# Display_Board_v2.net
KiCad netlist of a schematic drawn in EAGLE
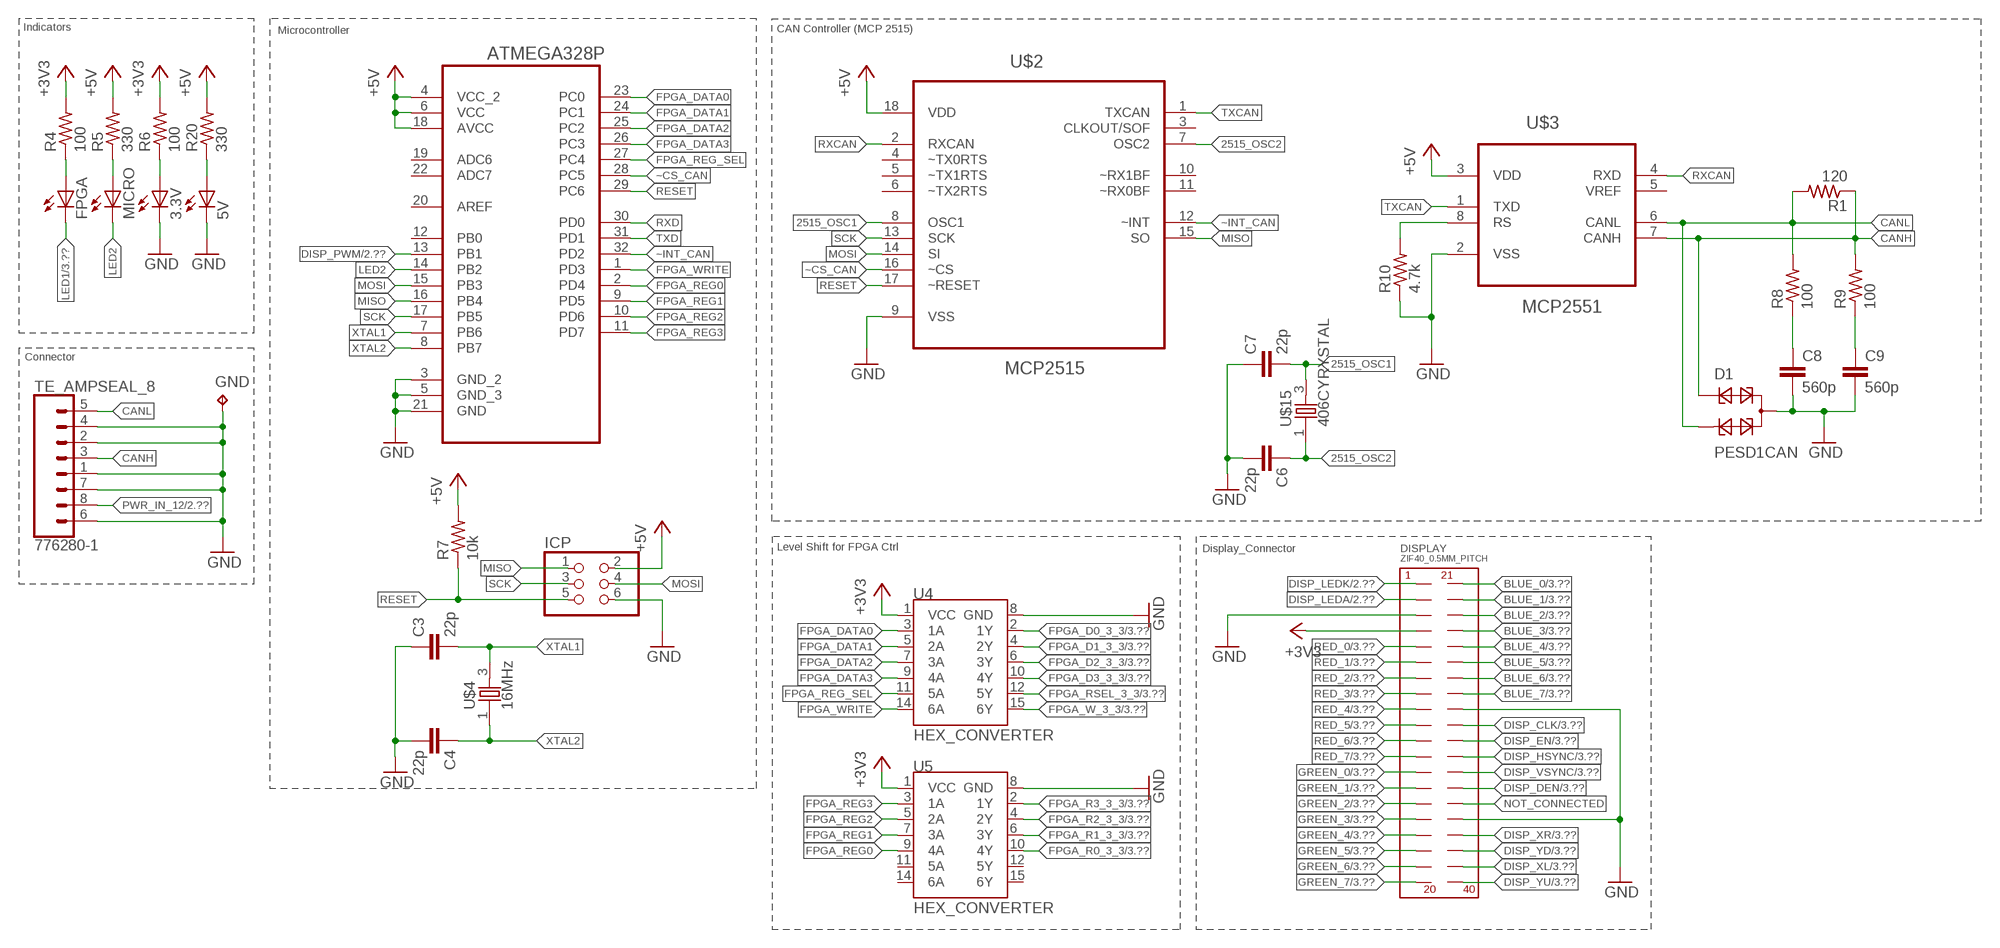
[diagram p0: schematic, sheet 1]
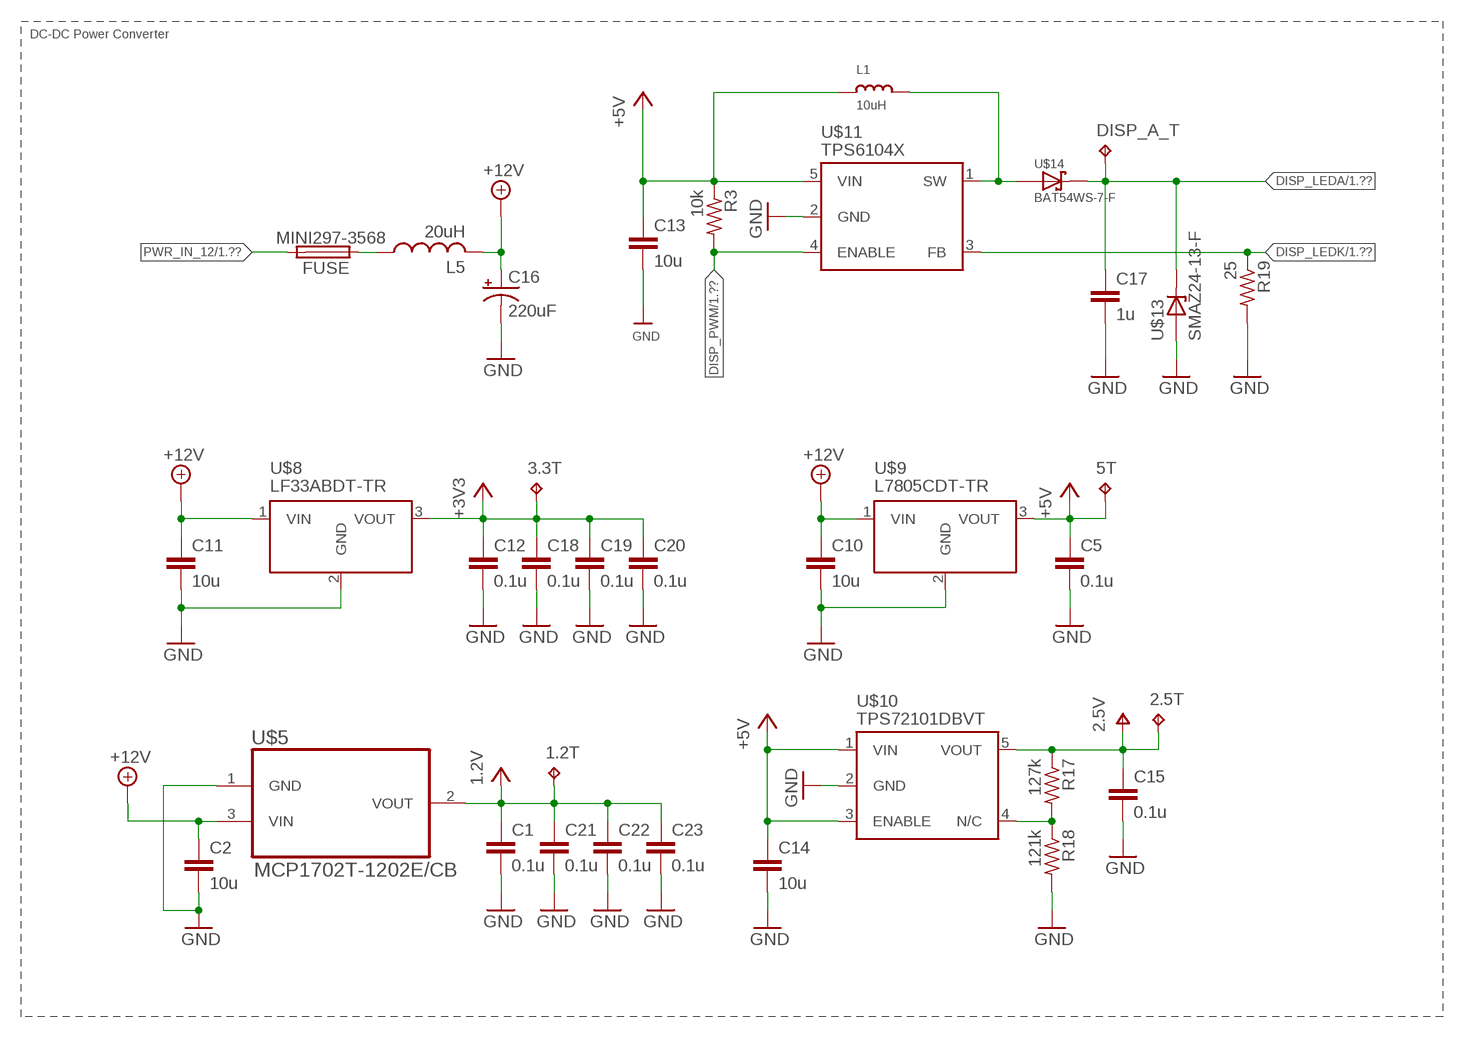
[diagram p1: schematic, sheet 2]
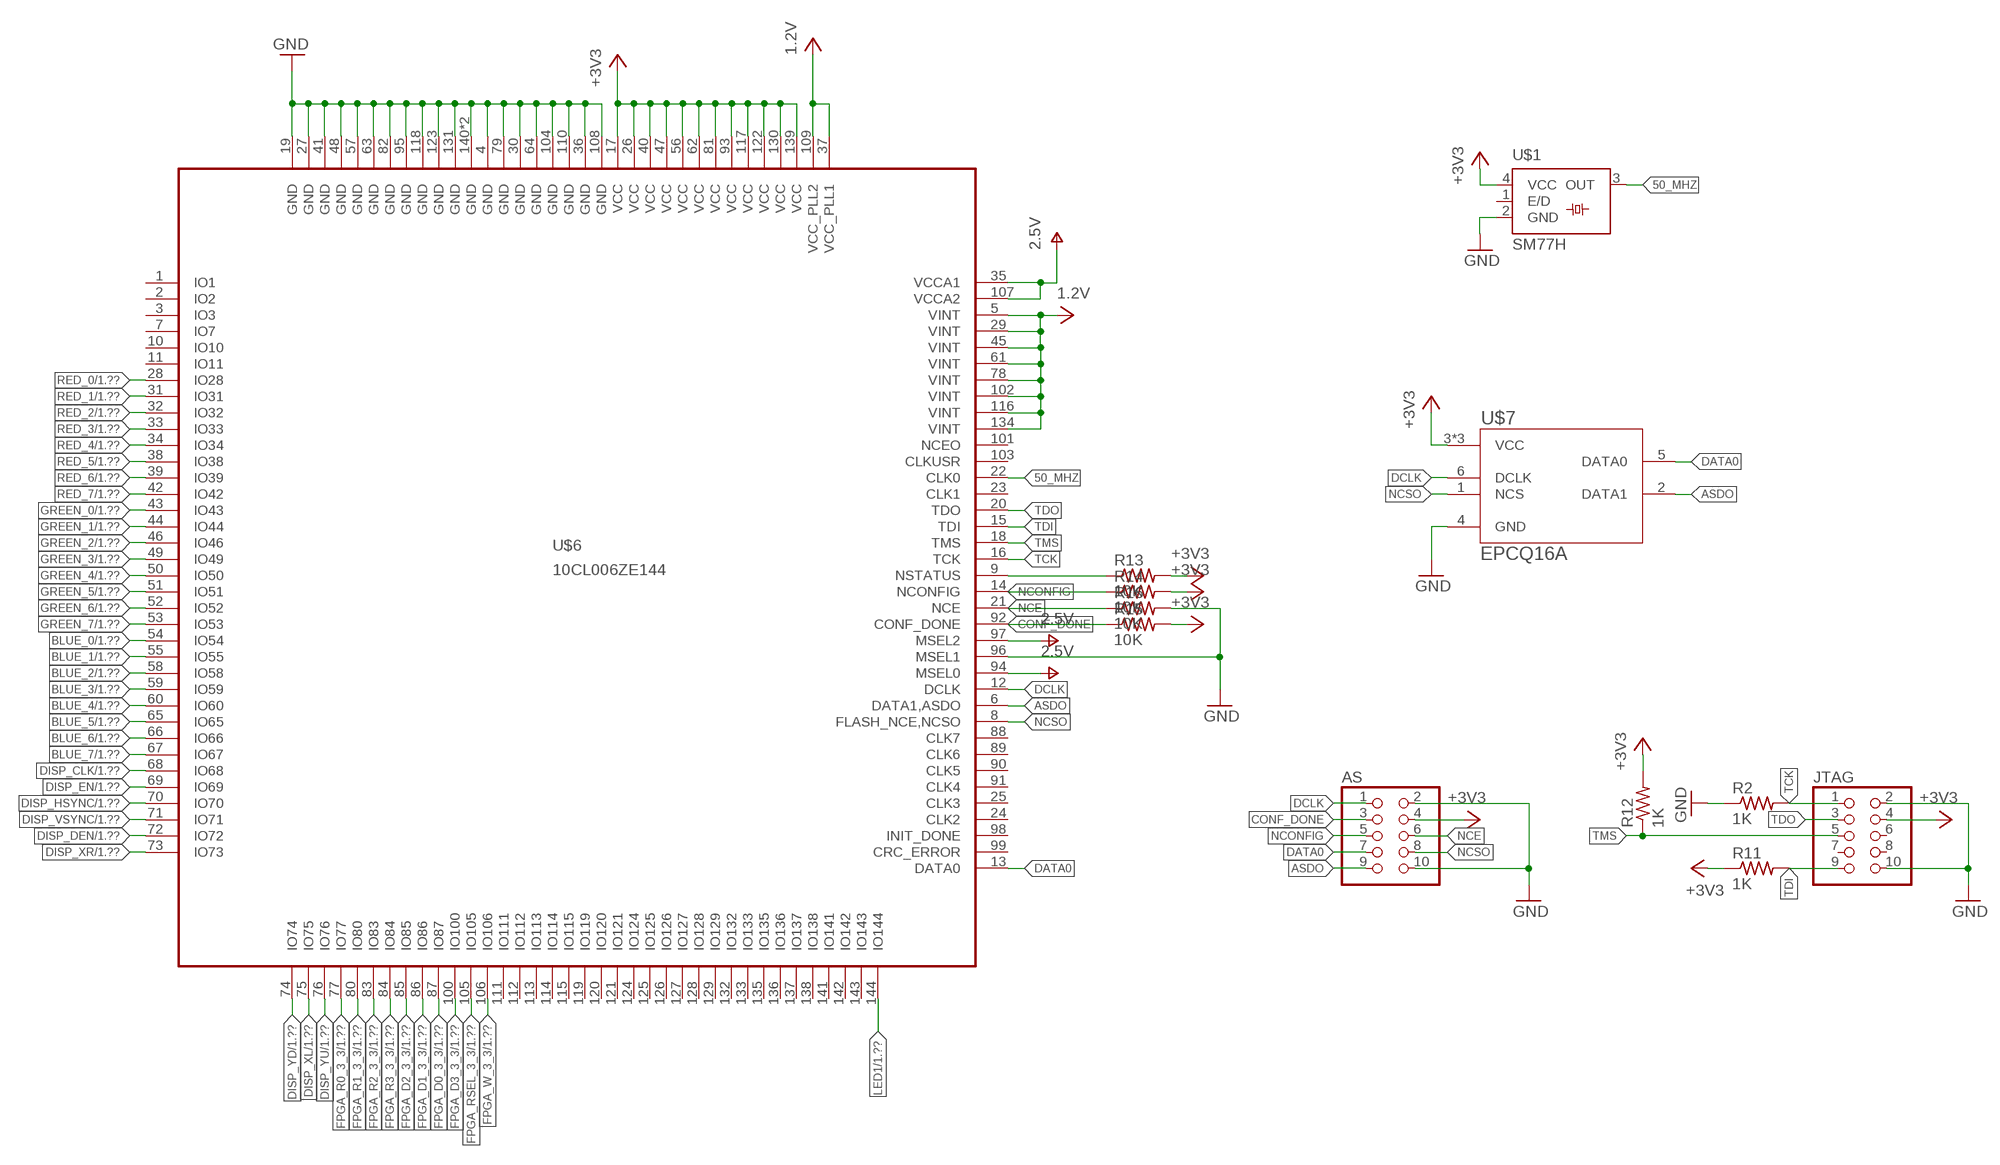
[diagram p2: schematic, sheet 3]

(export (version "E")
  (design (tool "Eeschema 10.0.6"))
  (components
    (comp (ref "AS")
      (value "PINHD-2X5")
      (footprint "eagle-import:2X05")
      (libsource (lib "eagle-import") (part "PINHD-2X5"))
    )
    (comp (ref "JTAG")
      (value "PINHD-2X5")
      (footprint "eagle-import:2X05")
      (libsource (lib "eagle-import") (part "PINHD-2X5"))
    )
    (comp (ref "R2")
      (value "1K")
      (footprint "eagle-import:R0805")
      (libsource (lib "eagle-import") (part "resistor_R-US_R0805"))
    )
    (comp (ref "R11")
      (value "1K")
      (footprint "eagle-import:R0805")
      (libsource (lib "eagle-import") (part "resistor_R-US_R0805"))
    )
    (comp (ref "R12")
      (value "1K")
      (footprint "eagle-import:R0805")
      (libsource (lib "eagle-import") (part "resistor_R-US_R0805"))
    )
    (comp (ref "R13")
      (value "10K")
      (footprint "eagle-import:R0805")
      (libsource (lib "eagle-import") (part "resistor_R-US_R0805"))
    )
    (comp (ref "R14")
      (value "10K")
      (footprint "eagle-import:R0805")
      (libsource (lib "eagle-import") (part "resistor_R-US_R0805"))
    )
    (comp (ref "R15")
      (value "10K")
      (footprint "eagle-import:R0805")
      (libsource (lib "eagle-import") (part "resistor_R-US_R0805"))
    )
    (comp (ref "R16")
      (value "10K")
      (footprint "eagle-import:R0805")
      (libsource (lib "eagle-import") (part "resistor_R-US_R0805"))
    )
    (comp (ref "U$1")
      (value "SM77H")
      (footprint "eagle-import:SM77H")
      (libsource (lib "eagle-import") (part "SM77H"))
    )
    (comp (ref "U$6")
      (value "10CL006ZE144")
      (footprint "eagle-import:EQFP144")
      (libsource (lib "eagle-import") (part "10CL006ZE144"))
    )
    (comp (ref "U$7")
      (value "EPCQ16A")
      (footprint "eagle-import:SOIC127P600X175-8N")
      (libsource (lib "eagle-import") (part "EPCQ16A"))
    )
    (comp (ref "1.2T")
      (value "TPTP12SQ")
      (footprint "eagle-import:TP12SQ")
      (libsource (lib "eagle-import") (part "TPTP12SQ"))
    )
    (comp (ref "2.5T")
      (value "TPTP12SQ")
      (footprint "eagle-import:TP12SQ")
      (libsource (lib "eagle-import") (part "TPTP12SQ"))
    )
    (comp (ref "3.3T")
      (value "TPTP12SQ")
      (footprint "eagle-import:TP12SQ")
      (libsource (lib "eagle-import") (part "TPTP12SQ"))
    )
    (comp (ref "5T")
      (value "TPTP12SQ")
      (footprint "eagle-import:TP12SQ")
      (libsource (lib "eagle-import") (part "TPTP12SQ"))
    )
    (comp (ref "C1")
      (value "0.1u")
      (footprint "eagle-import:C0805K")
      (libsource (lib "eagle-import") (part "C-EUC0805K"))
    )
    (comp (ref "C2")
      (value "10u")
      (footprint "eagle-import:C0805K")
      (libsource (lib "eagle-import") (part "C-EUC0805K"))
    )
    (comp (ref "C5")
      (value "0.1u")
      (footprint "eagle-import:C0805K")
      (libsource (lib "eagle-import") (part "C-EUC0805K"))
    )
    (comp (ref "C10")
      (value "10u")
      (footprint "eagle-import:C0805K")
      (libsource (lib "eagle-import") (part "C-EUC0805K"))
    )
    (comp (ref "C11")
      (value "10u")
      (footprint "eagle-import:C0805K")
      (libsource (lib "eagle-import") (part "C-EUC0805K"))
    )
    (comp (ref "C12")
      (value "0.1u")
      (footprint "eagle-import:C0805K")
      (libsource (lib "eagle-import") (part "C-EUC0805K"))
    )
    (comp (ref "C13")
      (value "10u")
      (footprint "eagle-import:C0805K")
      (libsource (lib "eagle-import") (part "C-EUC0805K"))
    )
    (comp (ref "C14")
      (value "10u")
      (footprint "eagle-import:C0805K")
      (libsource (lib "eagle-import") (part "C-EUC0805K"))
    )
    (comp (ref "C15")
      (value "0.1u")
      (footprint "eagle-import:C0805K")
      (libsource (lib "eagle-import") (part "C-EUC0805K"))
    )
    (comp (ref "C16")
      (value "220uF")
      (footprint "eagle-import:UD-6,3X7,7_NICHICON")
      (libsource (lib "eagle-import") (part "CPOL-USUD-6,3X7,7"))
    )
    (comp (ref "C17")
      (value "1u")
      (footprint "eagle-import:C0805K")
      (libsource (lib "eagle-import") (part "C-EUC0805K"))
    )
    (comp (ref "C18")
      (value "0.1u")
      (footprint "eagle-import:C0805K")
      (libsource (lib "eagle-import") (part "C-EUC0805K"))
    )
    (comp (ref "C19")
      (value "0.1u")
      (footprint "eagle-import:C0805K")
      (libsource (lib "eagle-import") (part "C-EUC0805K"))
    )
    (comp (ref "C20")
      (value "0.1u")
      (footprint "eagle-import:C0805K")
      (libsource (lib "eagle-import") (part "C-EUC0805K"))
    )
    (comp (ref "C21")
      (value "0.1u")
      (footprint "eagle-import:C0805K")
      (libsource (lib "eagle-import") (part "C-EUC0805K"))
    )
    (comp (ref "C22")
      (value "0.1u")
      (footprint "eagle-import:C0805K")
      (libsource (lib "eagle-import") (part "C-EUC0805K"))
    )
    (comp (ref "C23")
      (value "0.1u")
      (footprint "eagle-import:C0805K")
      (libsource (lib "eagle-import") (part "C-EUC0805K"))
    )
    (comp (ref "DISP_A_T")
      (value "TPTP12SQ")
      (footprint "eagle-import:TP12SQ")
      (libsource (lib "eagle-import") (part "TPTP12SQ"))
    )
    (comp (ref "FUSE")
      (value "MINI297-3568")
      (footprint "eagle-import:3568")
      (libsource (lib "eagle-import") (part "MINI297-3568"))
    )
    (comp (ref "L1")
      (value "10uH")
      (footprint "eagle-import:INDUCTOR_5X5MM_NR5040_NOTHERMALS")
      (libsource (lib "eagle-import") (part "INDUCTORNR5040"))
    )
    (comp (ref "L5")
      (value "20uH")
      (footprint "eagle-import:MSS7348")
      (libsource (lib "eagle-import") (part "MSS7348"))
    )
    (comp (ref "R3")
      (value "10k")
      (footprint "eagle-import:R0805")
      (libsource (lib "eagle-import") (part "rcl_334_R-US_R0805"))
    )
    (comp (ref "R17")
      (value "127k")
      (footprint "eagle-import:R0805")
      (libsource (lib "eagle-import") (part "rcl_334_R-US_R0805"))
    )
    (comp (ref "R18")
      (value "121k")
      (footprint "eagle-import:R0805")
      (libsource (lib "eagle-import") (part "rcl_334_R-US_R0805"))
    )
    (comp (ref "R19")
      (value "25")
      (footprint "eagle-import:R0805")
      (libsource (lib "eagle-import") (part "rcl_334_R-US_R0805"))
    )
    (comp (ref "U$5")
      (value "MCP1702T-1202E/CB")
      (footprint "eagle-import:SOT95P300X145-3N")
      (fields (field (name "MPN") "MCP1702T-1802E/CB"))
      (libsource (lib "eagle-import") (part "MCP1702T-1802E/CB"))
    )
    (comp (ref "U$8")
      (value "LF33ABDT-TR")
      (footprint "eagle-import:DPACK")
      (libsource (lib "eagle-import") (part "LF33ABDT-TR"))
    )
    (comp (ref "U$9")
      (value "L7805CDT-TR")
      (footprint "eagle-import:DPACK")
      (libsource (lib "eagle-import") (part "L7805CDT-TR"))
    )
    (comp (ref "U$10")
      (value "TPS72101DBVT")
      (footprint "eagle-import:SOT23-5L")
      (libsource (lib "eagle-import") (part "TPS72101DBVT"))
    )
    (comp (ref "U$11")
      (value "TPS6104X")
      (footprint "eagle-import:SOT23-5L")
      (libsource (lib "eagle-import") (part "TPS6104X"))
    )
    (comp (ref "U$13")
      (value "SMAZ24-13-F")
      (footprint "eagle-import:SMA_DIODE")
      (libsource (lib "eagle-import") (part "SMAZ24-13-F"))
    )
    (comp (ref "U$14")
      (value "BAT54WS-7-F")
      (footprint "eagle-import:SOD323")
      (libsource (lib "eagle-import") (part "BAT54WS-7-F"))
    )
    (comp (ref "3.3V")
      (value "LEDCHIP-LED0805")
      (footprint "eagle-import:CHIP-LED0805")
      (libsource (lib "eagle-import") (part "LEDCHIP-LED0805"))
    )
    (comp (ref "5V")
      (value "LEDCHIP-LED0805")
      (footprint "eagle-import:CHIP-LED0805")
      (libsource (lib "eagle-import") (part "LEDCHIP-LED0805"))
    )
    (comp (ref "ATMEGA328P")
      (value "ATMEGA328P-AU")
      (footprint "eagle-import:QFP80P900X900X120-32N")
      (libsource (lib "eagle-import") (part "ATMEGA328P-AU"))
    )
    (comp (ref "C3")
      (value "22p")
      (footprint "eagle-import:C0805K")
      (libsource (lib "eagle-import") (part "resistor_C-EUC0805K"))
    )
    (comp (ref "C4")
      (value "22p")
      (footprint "eagle-import:C0805K")
      (libsource (lib "eagle-import") (part "resistor_C-EUC0805K"))
    )
    (comp (ref "C6")
      (value "22p")
      (footprint "eagle-import:C0805K")
      (libsource (lib "eagle-import") (part "resistor_C-EUC0805K"))
    )
    (comp (ref "C7")
      (value "22p")
      (footprint "eagle-import:C0805K")
      (libsource (lib "eagle-import") (part "resistor_C-EUC0805K"))
    )
    (comp (ref "C8")
      (value "560p")
      (footprint "eagle-import:C0805K")
      (libsource (lib "eagle-import") (part "C-EUC0805K"))
    )
    (comp (ref "C9")
      (value "560p")
      (footprint "eagle-import:C0805K")
      (libsource (lib "eagle-import") (part "C-EUC0805K"))
    )
    (comp (ref "D1")
      (value "PESD1CAN")
      (footprint "eagle-import:SOT23")
      (libsource (lib "eagle-import") (part "PESD1CAN"))
    )
    (comp (ref "DISPLAY")
      (value "ZIF40_0.5MM_PITCH")
      (footprint "eagle-import:ZIF40")
      (libsource (lib "eagle-import") (part "ZIF40_0.5MM_PITCH"))
    )
    (comp (ref "FPGA")
      (value "LEDCHIP-LED0805")
      (footprint "eagle-import:CHIP-LED0805")
      (libsource (lib "eagle-import") (part "LEDCHIP-LED0805"))
    )
    (comp (ref "GND")
      (value "TPTP12SQ")
      (footprint "eagle-import:TP12SQ")
      (libsource (lib "eagle-import") (part "TPTP12SQ"))
    )
    (comp (ref "ICP")
      (value "PINHD-2X3")
      (footprint "eagle-import:2X03")
      (libsource (lib "eagle-import") (part "PINHD-2X3"))
    )
    (comp (ref "MICRO")
      (value "LEDCHIP-LED0805")
      (footprint "eagle-import:CHIP-LED0805")
      (libsource (lib "eagle-import") (part "LEDCHIP-LED0805"))
    )
    (comp (ref "R1")
      (value "120")
      (footprint "eagle-import:R0805")
      (libsource (lib "eagle-import") (part "R-US_R0805"))
    )
    (comp (ref "R4")
      (value "100")
      (footprint "eagle-import:R0805")
      (libsource (lib "eagle-import") (part "resistor_R-US_R0805"))
    )
    (comp (ref "R5")
      (value "330")
      (footprint "eagle-import:R0805")
      (libsource (lib "eagle-import") (part "resistor_R-US_R0805"))
    )
    (comp (ref "R6")
      (value "100")
      (footprint "eagle-import:R0805")
      (libsource (lib "eagle-import") (part "resistor_R-US_R0805"))
    )
    (comp (ref "R7")
      (value "10k")
      (footprint "eagle-import:R0805")
      (libsource (lib "eagle-import") (part "R-US_R0805"))
    )
    (comp (ref "R8")
      (value "100")
      (footprint "eagle-import:R0805")
      (libsource (lib "eagle-import") (part "R-US_R0805"))
    )
    (comp (ref "R9")
      (value "100")
      (footprint "eagle-import:R0805")
      (libsource (lib "eagle-import") (part "R-US_R0805"))
    )
    (comp (ref "R10")
      (value "4.7k")
      (footprint "eagle-import:R0805")
      (libsource (lib "eagle-import") (part "R-US_R0805"))
    )
    (comp (ref "R20")
      (value "330")
      (footprint "eagle-import:R0805")
      (libsource (lib "eagle-import") (part "resistor_R-US_R0805"))
    )
    (comp (ref "TE_AMPSEAL_8")
      (value "776280-1")
      (footprint "eagle-import:776280-1")
      (libsource (lib "eagle-import") (part "776280-1"))
    )
    (comp (ref "U$2")
      (value "MCP2515")
      (footprint "eagle-import:SOIC127P1034X264-18N")
      (fields (field (name "MPN") "MCP2515-I/SO"))
      (libsource (lib "eagle-import") (part "MCP2515-I/SO"))
    )
    (comp (ref "U$3")
      (value "MCP2551")
      (footprint "eagle-import:SOIC127P600X175-8N")
      (fields (field (name "MPN") "MCP2551-I/SN"))
      (libsource (lib "eagle-import") (part "MCP2551-I/SN"))
    )
    (comp (ref "U$4")
      (value "16MHz")
      (footprint "eagle-import:CTS406")
      (libsource (lib "eagle-import") (part "406CYRYSTAL"))
    )
    (comp (ref "U$15")
      (value "406CYRYSTAL")
      (footprint "eagle-import:CTS406")
      (libsource (lib "eagle-import") (part "406CYRYSTAL"))
    )
    (comp (ref "U4")
      (value "HEX_CONVERTER")
      (footprint "eagle-import:SO016")
      (libsource (lib "eagle-import") (part "HEX_CONVERTER"))
    )
    (comp (ref "U5")
      (value "HEX_CONVERTER")
      (footprint "eagle-import:SO016")
      (libsource (lib "eagle-import") (part "HEX_CONVERTER"))
    )
  )
  (nets
    (net (code "1") (name "+3V3") (class "Default")
      (node (ref "3.3T") (pin "TP") (pinfunction "TP_TP") (pintype "input"))
      (node (ref "AS") (pin "4") (pinfunction "4_4") (pintype "passive"))
      (node (ref "C12") (pin "1") (pinfunction "1_1") (pintype "passive"))
      (node (ref "C18") (pin "1") (pinfunction "1_1") (pintype "passive"))
      (node (ref "C19") (pin "1") (pinfunction "1_1") (pintype "passive"))
      (node (ref "C20") (pin "1") (pinfunction "1_1") (pintype "passive"))
      (node (ref "DISPLAY") (pin "P$4") (pinfunction "P$4_P$4") (pintype "bidirectional"))
      (node (ref "JTAG") (pin "4") (pinfunction "4_4") (pintype "passive"))
      (node (ref "R11") (pin "1") (pinfunction "1_1") (pintype "passive"))
      (node (ref "R12") (pin "2") (pinfunction "2_2") (pintype "passive"))
      (node (ref "R13") (pin "2") (pinfunction "2_2") (pintype "passive"))
      (node (ref "R14") (pin "2") (pinfunction "2_2") (pintype "passive"))
      (node (ref "R15") (pin "2") (pinfunction "2_2") (pintype "passive"))
      (node (ref "R4") (pin "2") (pinfunction "2_2") (pintype "passive"))
      (node (ref "R6") (pin "2") (pinfunction "2_2") (pintype "passive"))
      (node (ref "U$1") (pin "4") (pinfunction "VCC_4") (pintype "power_in"))
      (node (ref "U$6") (pin "117") (pinfunction "VCC_117") (pintype "power_in"))
      (node (ref "U$6") (pin "122") (pinfunction "VCC_122") (pintype "power_in"))
      (node (ref "U$6") (pin "130") (pinfunction "VCC_130") (pintype "power_in"))
      (node (ref "U$6") (pin "139") (pinfunction "VCC_139") (pintype "power_in"))
      (node (ref "U$6") (pin "17") (pinfunction "VCC_17") (pintype "power_in"))
      (node (ref "U$6") (pin "26") (pinfunction "VCC_26") (pintype "power_in"))
      (node (ref "U$6") (pin "40") (pinfunction "VCC_40") (pintype "power_in"))
      (node (ref "U$6") (pin "47") (pinfunction "VCC_47") (pintype "power_in"))
      (node (ref "U$6") (pin "56") (pinfunction "VCC_56") (pintype "power_in"))
      (node (ref "U$6") (pin "62") (pinfunction "VCC_62") (pintype "power_in"))
      (node (ref "U$6") (pin "81") (pinfunction "VCC_81") (pintype "power_in"))
      (node (ref "U$6") (pin "93") (pinfunction "VCC_93") (pintype "power_in"))
      (node (ref "U$7") (pin "3") (pinfunction "VCC_3") (pintype "power_in"))
      (node (ref "U$7") (pin "7") (pinfunction "VCC_7") (pintype "power_in"))
      (node (ref "U$7") (pin "8") (pinfunction "VCC_8") (pintype "power_in"))
      (node (ref "U$8") (pin "3") (pinfunction "VOUT_3") (pintype "bidirectional"))
      (node (ref "U4") (pin "1") (pinfunction "VCC_1") (pintype "bidirectional"))
      (node (ref "U5") (pin "1") (pinfunction "VCC_1") (pintype "bidirectional"))
    )
    (net (code "2") (name "+5V") (class "Default")
      (node (ref "5T") (pin "TP") (pinfunction "TP_TP") (pintype "input"))
      (node (ref "ATMEGA328P") (pin "18") (pinfunction "AVCC_18") (pintype "power_in"))
      (node (ref "ATMEGA328P") (pin "4") (pinfunction "VCC_2_4") (pintype "power_in"))
      (node (ref "ATMEGA328P") (pin "6") (pinfunction "VCC_6") (pintype "power_in"))
      (node (ref "C13") (pin "1") (pinfunction "1_1") (pintype "passive"))
      (node (ref "C14") (pin "1") (pinfunction "1_1") (pintype "passive"))
      (node (ref "C5") (pin "1") (pinfunction "1_1") (pintype "passive"))
      (node (ref "ICP") (pin "2") (pinfunction "2_2") (pintype "passive"))
      (node (ref "L1") (pin "P$1") (pinfunction "1_P$1") (pintype "passive"))
      (node (ref "R20") (pin "2") (pinfunction "2_2") (pintype "passive"))
      (node (ref "R3") (pin "1") (pinfunction "1_1") (pintype "passive"))
      (node (ref "R5") (pin "2") (pinfunction "2_2") (pintype "passive"))
      (node (ref "R7") (pin "2") (pinfunction "2_2") (pintype "passive"))
      (node (ref "U$10") (pin "1") (pinfunction "VIN_1") (pintype "bidirectional"))
      (node (ref "U$10") (pin "3") (pinfunction "ENABLE_3") (pintype "bidirectional"))
      (node (ref "U$11") (pin "5") (pinfunction "VIN_5") (pintype "bidirectional"))
      (node (ref "U$2") (pin "18") (pinfunction "VDD_18") (pintype "power_in"))
      (node (ref "U$3") (pin "3") (pinfunction "VDD_3") (pintype "power_in"))
      (node (ref "U$9") (pin "3") (pinfunction "VOUT_3") (pintype "bidirectional"))
    )
    (net (code "3") (name "+12V") (class "Default")
      (node (ref "C10") (pin "1") (pinfunction "1_1") (pintype "passive"))
      (node (ref "C11") (pin "1") (pinfunction "1_1") (pintype "passive"))
      (node (ref "C16") (pin "+") (pinfunction "+_+") (pintype "passive"))
      (node (ref "C2") (pin "1") (pinfunction "1_1") (pintype "passive"))
      (node (ref "L5") (pin "P$2") (pinfunction "2_P$2") (pintype "passive"))
      (node (ref "U$5") (pin "3") (pinfunction "VIN_3") (pintype "power_in"))
      (node (ref "U$8") (pin "1") (pinfunction "VIN_1") (pintype "bidirectional"))
      (node (ref "U$9") (pin "1") (pinfunction "VIN_1") (pintype "bidirectional"))
    )
    (net (code "4") (name "50_MHZ") (class "Default")
      (node (ref "U$1") (pin "3") (pinfunction "OUT_3") (pintype "output"))
      (node (ref "U$6") (pin "22") (pinfunction "CLK0_22") (pintype "power_in"))
    )
    (net (code "5") (name "2515_OSC1") (class "Default")
      (node (ref "C7") (pin "2") (pinfunction "2_2") (pintype "passive"))
      (node (ref "U$15") (pin "3") (pinfunction "2_3") (pintype "passive"))
      (node (ref "U$2") (pin "8") (pinfunction "OSC1_8") (pintype "input"))
    )
    (net (code "6") (name "2515_OSC2") (class "Default")
      (node (ref "C6") (pin "1") (pinfunction "1_1") (pintype "passive"))
      (node (ref "U$15") (pin "1") (pinfunction "1_1") (pintype "passive"))
      (node (ref "U$2") (pin "7") (pinfunction "OSC2_7") (pintype "output"))
    )
    (net (code "7") (name "ASDO") (class "Default")
      (node (ref "AS") (pin "9") (pinfunction "9_9") (pintype "passive"))
      (node (ref "U$6") (pin "6") (pinfunction "DATA1,ASDO_6") (pintype "input"))
      (node (ref "U$7") (pin "2") (pinfunction "DATA1_2") (pintype "output"))
    )
    (net (code "8") (name "BLUE_0") (class "Default")
      (node (ref "DISPLAY") (pin "P$21") (pinfunction "P$21_P$21") (pintype "bidirectional"))
      (node (ref "U$6") (pin "54") (pinfunction "IO54_54") (pintype "bidirectional"))
    )
    (net (code "9") (name "BLUE_1") (class "Default")
      (node (ref "DISPLAY") (pin "P$22") (pinfunction "P$22_P$22") (pintype "bidirectional"))
      (node (ref "U$6") (pin "55") (pinfunction "IO55_55") (pintype "bidirectional"))
    )
    (net (code "10") (name "BLUE_2") (class "Default")
      (node (ref "DISPLAY") (pin "P$23") (pinfunction "P$23_P$23") (pintype "bidirectional"))
      (node (ref "U$6") (pin "58") (pinfunction "IO58_58") (pintype "bidirectional"))
    )
    (net (code "11") (name "BLUE_3") (class "Default")
      (node (ref "DISPLAY") (pin "P$24") (pinfunction "P$24_P$24") (pintype "bidirectional"))
      (node (ref "U$6") (pin "59") (pinfunction "IO59_59") (pintype "bidirectional"))
    )
    (net (code "12") (name "BLUE_4") (class "Default")
      (node (ref "DISPLAY") (pin "P$25") (pinfunction "P$25_P$25") (pintype "bidirectional"))
      (node (ref "U$6") (pin "60") (pinfunction "IO60_60") (pintype "bidirectional"))
    )
    (net (code "13") (name "BLUE_5") (class "Default")
      (node (ref "DISPLAY") (pin "P$26") (pinfunction "P$26_P$26") (pintype "bidirectional"))
      (node (ref "U$6") (pin "65") (pinfunction "IO65_65") (pintype "bidirectional"))
    )
    (net (code "14") (name "BLUE_6") (class "Default")
      (node (ref "DISPLAY") (pin "P$27") (pinfunction "P$27_P$27") (pintype "bidirectional"))
      (node (ref "U$6") (pin "66") (pinfunction "IO66_66") (pintype "bidirectional"))
    )
    (net (code "15") (name "BLUE_7") (class "Default")
      (node (ref "DISPLAY") (pin "P$28") (pinfunction "P$28_P$28") (pintype "bidirectional"))
      (node (ref "U$6") (pin "67") (pinfunction "IO67_67") (pintype "bidirectional"))
    )
    (net (code "16") (name "CANH") (class "Default")
      (node (ref "D1") (pin "1") (pinfunction "1_1") (pintype "passive"))
      (node (ref "R1") (pin "1") (pinfunction "1_1") (pintype "passive"))
      (node (ref "R9") (pin "2") (pinfunction "2_2") (pintype "passive"))
      (node (ref "TE_AMPSEAL_8") (pin "3") (pinfunction "5_3") (pintype "passive"))
      (node (ref "U$3") (pin "7") (pinfunction "CANH_7") (pintype "bidirectional"))
    )
    (net (code "17") (name "CANL") (class "Default")
      (node (ref "D1") (pin "2") (pinfunction "2_2") (pintype "passive"))
      (node (ref "R1") (pin "2") (pinfunction "2_2") (pintype "passive"))
      (node (ref "R8") (pin "2") (pinfunction "2_2") (pintype "passive"))
      (node (ref "TE_AMPSEAL_8") (pin "5") (pinfunction "8_5") (pintype "passive"))
      (node (ref "U$3") (pin "6") (pinfunction "CANL_6") (pintype "bidirectional"))
    )
    (net (code "18") (name "CLK1") (class "Default")
      (node (ref "U$6") (pin "23") (pinfunction "CLK1_23") (pintype "power_in"))
    )
    (net (code "19") (name "CLKUSR") (class "Default")
      (node (ref "U$6") (pin "103") (pinfunction "CLKUSR_103") (pintype "power_in"))
    )
    (net (code "20") (name "CONF_DONE") (class "Default")
      (node (ref "AS") (pin "3") (pinfunction "3_3") (pintype "passive"))
      (node (ref "R15") (pin "1") (pinfunction "1_1") (pintype "passive"))
      (node (ref "U$6") (pin "92") (pinfunction "CONF_DONE_92") (pintype "input"))
    )
    (net (code "21") (name "DATA0") (class "Default")
      (node (ref "AS") (pin "7") (pinfunction "7_7") (pintype "passive"))
      (node (ref "U$6") (pin "13") (pinfunction "DATA0_13") (pintype "power_in"))
      (node (ref "U$7") (pin "5") (pinfunction "DATA0_5") (pintype "output"))
    )
    (net (code "22") (name "DCLK") (class "Default")
      (node (ref "AS") (pin "1") (pinfunction "1_1") (pintype "passive"))
      (node (ref "U$6") (pin "12") (pinfunction "DCLK_12") (pintype "input"))
      (node (ref "U$7") (pin "6") (pinfunction "DCLK_6") (pintype "input"))
    )
    (net (code "23") (name "DISP_CLK") (class "Default")
      (node (ref "DISPLAY") (pin "P$30") (pinfunction "P$30_P$30") (pintype "bidirectional"))
      (node (ref "U$6") (pin "68") (pinfunction "IO68_68") (pintype "bidirectional"))
    )
    (net (code "24") (name "DISP_DEN") (class "Default")
      (node (ref "DISPLAY") (pin "P$34") (pinfunction "P$34_P$34") (pintype "bidirectional"))
      (node (ref "U$6") (pin "72") (pinfunction "IO72_72") (pintype "bidirectional"))
    )
    (net (code "25") (name "DISP_EN") (class "Default")
      (node (ref "DISPLAY") (pin "P$31") (pinfunction "P$31_P$31") (pintype "bidirectional"))
      (node (ref "U$6") (pin "69") (pinfunction "IO69_69") (pintype "bidirectional"))
    )
    (net (code "26") (name "DISP_HSYNC") (class "Default")
      (node (ref "DISPLAY") (pin "P$32") (pinfunction "P$32_P$32") (pintype "bidirectional"))
      (node (ref "U$6") (pin "70") (pinfunction "IO70_70") (pintype "bidirectional"))
    )
    (net (code "27") (name "DISP_LEDA") (class "Default")
      (node (ref "C17") (pin "1") (pinfunction "1_1") (pintype "passive"))
      (node (ref "DISPLAY") (pin "P$2") (pinfunction "P$2_P$2") (pintype "bidirectional"))
      (node (ref "DISP_A_T") (pin "TP") (pinfunction "TP_TP") (pintype "input"))
      (node (ref "U$13") (pin "C") (pinfunction "C_C") (pintype "bidirectional"))
      (node (ref "U$14") (pin "1") (pinfunction "C_1") (pintype "bidirectional"))
    )
    (net (code "28") (name "DISP_LEDK") (class "Default")
      (node (ref "DISPLAY") (pin "P$1") (pinfunction "P$1_P$1") (pintype "bidirectional"))
      (node (ref "R19") (pin "1") (pinfunction "1_1") (pintype "passive"))
      (node (ref "U$11") (pin "3") (pinfunction "FB_3") (pintype "bidirectional"))
    )
    (net (code "29") (name "DISP_PWM") (class "Default")
      (node (ref "ATMEGA328P") (pin "13") (pinfunction "PB1_13") (pintype "bidirectional"))
      (node (ref "R3") (pin "2") (pinfunction "2_2") (pintype "passive"))
      (node (ref "U$11") (pin "4") (pinfunction "ENABLE_4") (pintype "bidirectional"))
    )
    (net (code "30") (name "DISP_VSYNC") (class "Default")
      (node (ref "DISPLAY") (pin "P$33") (pinfunction "P$33_P$33") (pintype "bidirectional"))
      (node (ref "U$6") (pin "71") (pinfunction "IO71_71") (pintype "bidirectional"))
    )
    (net (code "31") (name "DISP_XL") (class "Default")
      (node (ref "DISPLAY") (pin "P$39") (pinfunction "P$39_P$39") (pintype "bidirectional"))
      (node (ref "U$6") (pin "75") (pinfunction "IO75_75") (pintype "bidirectional"))
    )
    (net (code "32") (name "DISP_XR") (class "Default")
      (node (ref "DISPLAY") (pin "P$37") (pinfunction "P$37_P$37") (pintype "bidirectional"))
      (node (ref "U$6") (pin "73") (pinfunction "IO73_73") (pintype "bidirectional"))
    )
    (net (code "33") (name "DISP_YD") (class "Default")
      (node (ref "DISPLAY") (pin "P$38") (pinfunction "P$38_P$38") (pintype "bidirectional"))
      (node (ref "U$6") (pin "74") (pinfunction "IO74_74") (pintype "bidirectional"))
    )
    (net (code "34") (name "DISP_YU") (class "Default")
      (node (ref "DISPLAY") (pin "P$40") (pinfunction "P$40_P$40") (pintype "bidirectional"))
      (node (ref "U$6") (pin "76") (pinfunction "IO76_76") (pintype "bidirectional"))
    )
    (net (code "35") (name "FPGA_D0_3_3") (class "Default")
      (node (ref "U$6") (pin "87") (pinfunction "IO87_87") (pintype "bidirectional"))
      (node (ref "U4") (pin "2") (pinfunction "1Y_2") (pintype "bidirectional"))
    )
    (net (code "36") (name "FPGA_D1_3_3") (class "Default")
      (node (ref "U$6") (pin "86") (pinfunction "IO86_86") (pintype "bidirectional"))
      (node (ref "U4") (pin "4") (pinfunction "2Y_4") (pintype "bidirectional"))
    )
    (net (code "37") (name "FPGA_D2_3_3") (class "Default")
      (node (ref "U$6") (pin "85") (pinfunction "IO85_85") (pintype "bidirectional"))
      (node (ref "U4") (pin "6") (pinfunction "3Y_6") (pintype "bidirectional"))
    )
    (net (code "38") (name "FPGA_D3_3_3") (class "Default")
      (node (ref "U$6") (pin "100") (pinfunction "IO100_100") (pintype "power_in"))
      (node (ref "U4") (pin "10") (pinfunction "4Y_10") (pintype "bidirectional"))
    )
    (net (code "39") (name "FPGA_DATA0") (class "Default")
      (node (ref "ATMEGA328P") (pin "23") (pinfunction "PC0_23") (pintype "bidirectional"))
      (node (ref "U4") (pin "3") (pinfunction "1A_3") (pintype "bidirectional"))
    )
    (net (code "40") (name "FPGA_DATA1") (class "Default")
      (node (ref "ATMEGA328P") (pin "24") (pinfunction "PC1_24") (pintype "bidirectional"))
      (node (ref "U4") (pin "5") (pinfunction "2A_5") (pintype "bidirectional"))
    )
    (net (code "41") (name "FPGA_DATA2") (class "Default")
      (node (ref "ATMEGA328P") (pin "25") (pinfunction "PC2_25") (pintype "bidirectional"))
      (node (ref "U4") (pin "7") (pinfunction "3A_7") (pintype "bidirectional"))
    )
    (net (code "42") (name "FPGA_DATA3") (class "Default")
      (node (ref "ATMEGA328P") (pin "26") (pinfunction "PC3_26") (pintype "bidirectional"))
      (node (ref "U4") (pin "9") (pinfunction "4A_9") (pintype "bidirectional"))
    )
    (net (code "43") (name "FPGA_R0_3_3") (class "Default")
      (node (ref "U$6") (pin "77") (pinfunction "IO77_77") (pintype "bidirectional"))
      (node (ref "U5") (pin "10") (pinfunction "4Y_10") (pintype "bidirectional"))
    )
    (net (code "44") (name "FPGA_R1_3_3") (class "Default")
      (node (ref "U$6") (pin "80") (pinfunction "IO80_80") (pintype "bidirectional"))
      (node (ref "U5") (pin "6") (pinfunction "3Y_6") (pintype "bidirectional"))
    )
    (net (code "45") (name "FPGA_R2_3_3") (class "Default")
      (node (ref "U$6") (pin "83") (pinfunction "IO83_83") (pintype "bidirectional"))
      (node (ref "U5") (pin "4") (pinfunction "2Y_4") (pintype "bidirectional"))
    )
    (net (code "46") (name "FPGA_R3_3_3") (class "Default")
      (node (ref "U$6") (pin "84") (pinfunction "IO84_84") (pintype "bidirectional"))
      (node (ref "U5") (pin "2") (pinfunction "1Y_2") (pintype "bidirectional"))
    )
    (net (code "47") (name "FPGA_REG0") (class "Default")
      (node (ref "ATMEGA328P") (pin "2") (pinfunction "PD4_2") (pintype "bidirectional"))
      (node (ref "U5") (pin "9") (pinfunction "4A_9") (pintype "bidirectional"))
    )
    (net (code "48") (name "FPGA_REG1") (class "Default")
      (node (ref "ATMEGA328P") (pin "9") (pinfunction "PD5_9") (pintype "bidirectional"))
      (node (ref "U5") (pin "7") (pinfunction "3A_7") (pintype "bidirectional"))
    )
    (net (code "49") (name "FPGA_REG2") (class "Default")
      (node (ref "ATMEGA328P") (pin "10") (pinfunction "PD6_10") (pintype "bidirectional"))
      (node (ref "U5") (pin "5") (pinfunction "2A_5") (pintype "bidirectional"))
    )
    (net (code "50") (name "FPGA_REG3") (class "Default")
      (node (ref "ATMEGA328P") (pin "11") (pinfunction "PD7_11") (pintype "bidirectional"))
      (node (ref "U5") (pin "3") (pinfunction "1A_3") (pintype "bidirectional"))
    )
    (net (code "51") (name "FPGA_REG_SEL") (class "Default")
      (node (ref "ATMEGA328P") (pin "27") (pinfunction "PC4_27") (pintype "bidirectional"))
      (node (ref "U4") (pin "11") (pinfunction "5A_11") (pintype "bidirectional"))
    )
    (net (code "52") (name "FPGA_RSEL_3_3") (class "Default")
      (node (ref "U$6") (pin "105") (pinfunction "IO105_105") (pintype "bidirectional"))
      (node (ref "U4") (pin "12") (pinfunction "5Y_12") (pintype "bidirectional"))
    )
    (net (code "53") (name "FPGA_WRITE") (class "Default")
      (node (ref "ATMEGA328P") (pin "1") (pinfunction "PD3_1") (pintype "bidirectional"))
      (node (ref "U4") (pin "14") (pinfunction "6A_14") (pintype "bidirectional"))
    )
    (net (code "54") (name "FPGA_W_3_3") (class "Default")
      (node (ref "U$6") (pin "106") (pinfunction "IO106_106") (pintype "bidirectional"))
      (node (ref "U4") (pin "15") (pinfunction "6Y_15") (pintype "bidirectional"))
    )
    (net (code "55") (name "GND") (class "Default")
      (node (ref "3.3V") (pin "C") (pinfunction "C_C") (pintype "passive"))
      (node (ref "5V") (pin "C") (pinfunction "C_C") (pintype "passive"))
      (node (ref "AS") (pin "10") (pinfunction "10_10") (pintype "passive"))
      (node (ref "AS") (pin "2") (pinfunction "2_2") (pintype "passive"))
      (node (ref "ATMEGA328P") (pin "21") (pinfunction "GND_21") (pintype "passive"))
      (node (ref "ATMEGA328P") (pin "3") (pinfunction "GND_2_3") (pintype "passive"))
      (node (ref "ATMEGA328P") (pin "5") (pinfunction "GND_3_5") (pintype "passive"))
      (node (ref "C1") (pin "2") (pinfunction "2_2") (pintype "passive"))
      (node (ref "C10") (pin "2") (pinfunction "2_2") (pintype "passive"))
      (node (ref "C11") (pin "2") (pinfunction "2_2") (pintype "passive"))
      (node (ref "C12") (pin "2") (pinfunction "2_2") (pintype "passive"))
      (node (ref "C13") (pin "2") (pinfunction "2_2") (pintype "passive"))
      (node (ref "C14") (pin "2") (pinfunction "2_2") (pintype "passive"))
      (node (ref "C15") (pin "2") (pinfunction "2_2") (pintype "passive"))
      (node (ref "C16") (pin "-") (pinfunction "-_-") (pintype "passive"))
      (node (ref "C17") (pin "2") (pinfunction "2_2") (pintype "passive"))
      (node (ref "C18") (pin "2") (pinfunction "2_2") (pintype "passive"))
      (node (ref "C19") (pin "2") (pinfunction "2_2") (pintype "passive"))
      (node (ref "C2") (pin "2") (pinfunction "2_2") (pintype "passive"))
      (node (ref "C20") (pin "2") (pinfunction "2_2") (pintype "passive"))
      (node (ref "C21") (pin "2") (pinfunction "2_2") (pintype "passive"))
      (node (ref "C22") (pin "2") (pinfunction "2_2") (pintype "passive"))
      (node (ref "C23") (pin "2") (pinfunction "2_2") (pintype "passive"))
      (node (ref "C3") (pin "1") (pinfunction "1_1") (pintype "passive"))
      (node (ref "C4") (pin "2") (pinfunction "2_2") (pintype "passive"))
      (node (ref "C5") (pin "2") (pinfunction "2_2") (pintype "passive"))
      (node (ref "C6") (pin "2") (pinfunction "2_2") (pintype "passive"))
      (node (ref "C7") (pin "1") (pinfunction "1_1") (pintype "passive"))
      (node (ref "C8") (pin "2") (pinfunction "2_2") (pintype "passive"))
      (node (ref "C9") (pin "2") (pinfunction "2_2") (pintype "passive"))
      (node (ref "D1") (pin "3") (pinfunction "3_3") (pintype "passive"))
      (node (ref "DISPLAY") (pin "P$29") (pinfunction "P$29_P$29") (pintype "bidirectional"))
      (node (ref "DISPLAY") (pin "P$3") (pinfunction "P$3_P$3") (pintype "bidirectional"))
      (node (ref "DISPLAY") (pin "P$36") (pinfunction "P$36_P$36") (pintype "bidirectional"))
      (node (ref "GND") (pin "TP") (pinfunction "TP_TP") (pintype "input"))
      (node (ref "ICP") (pin "6") (pinfunction "6_6") (pintype "passive"))
      (node (ref "JTAG") (pin "10") (pinfunction "10_10") (pintype "passive"))
      (node (ref "JTAG") (pin "2") (pinfunction "2_2") (pintype "passive"))
      (node (ref "R10") (pin "1") (pinfunction "1_1") (pintype "passive"))
      (node (ref "R16") (pin "2") (pinfunction "2_2") (pintype "passive"))
      (node (ref "R18") (pin "2") (pinfunction "2_2") (pintype "passive"))
      (node (ref "R19") (pin "2") (pinfunction "2_2") (pintype "passive"))
      (node (ref "R2") (pin "1") (pinfunction "1_1") (pintype "passive"))
      (node (ref "TE_AMPSEAL_8") (pin "1") (pinfunction "4_1") (pintype "passive"))
      (node (ref "TE_AMPSEAL_8") (pin "2") (pinfunction "6_2") (pintype "passive"))
      (node (ref "TE_AMPSEAL_8") (pin "4") (pinfunction "7_4") (pintype "passive"))
      (node (ref "TE_AMPSEAL_8") (pin "6") (pinfunction "1_6") (pintype "passive"))
      (node (ref "TE_AMPSEAL_8") (pin "7") (pinfunction "3_7") (pintype "passive"))
      (node (ref "U$1") (pin "2") (pinfunction "GND_2") (pintype "power_in"))
      (node (ref "U$10") (pin "2") (pinfunction "GND_2") (pintype "bidirectional"))
      (node (ref "U$11") (pin "2") (pinfunction "GND_2") (pintype "bidirectional"))
      (node (ref "U$13") (pin "A") (pinfunction "A_A") (pintype "input"))
      (node (ref "U$2") (pin "9") (pinfunction "VSS_9") (pintype "power_in"))
      (node (ref "U$3") (pin "2") (pinfunction "VSS_2") (pintype "passive"))
      (node (ref "U$5") (pin "1") (pinfunction "GND_1") (pintype "passive"))
      (node (ref "U$6") (pin "104") (pinfunction "GND_104") (pintype "power_in"))
      (node (ref "U$6") (pin "108") (pinfunction "GND_108") (pintype "power_in"))
      (node (ref "U$6") (pin "110") (pinfunction "GND_110") (pintype "power_in"))
      (node (ref "U$6") (pin "118") (pinfunction "GND_118") (pintype "power_in"))
      (node (ref "U$6") (pin "123") (pinfunction "GND_123") (pintype "power_in"))
      (node (ref "U$6") (pin "131") (pinfunction "GND_131") (pintype "power_in"))
      (node (ref "U$6") (pin "140") (pinfunction "GND_140") (pintype "power_in"))
      (node (ref "U$6") (pin "19") (pinfunction "GND_19") (pintype "power_in"))
      (node (ref "U$6") (pin "27") (pinfunction "GND_27") (pintype "power_in"))
      (node (ref "U$6") (pin "30") (pinfunction "GND_30") (pintype "power_in"))
      (node (ref "U$6") (pin "36") (pinfunction "GND_36") (pintype "power_in"))
      (node (ref "U$6") (pin "4") (pinfunction "GND_4") (pintype "power_in"))
      (node (ref "U$6") (pin "41") (pinfunction "GND_41") (pintype "power_in"))
      (node (ref "U$6") (pin "48") (pinfunction "GND_48") (pintype "power_in"))
      (node (ref "U$6") (pin "57") (pinfunction "GND_57") (pintype "power_in"))
      (node (ref "U$6") (pin "63") (pinfunction "GND_63") (pintype "power_in"))
      (node (ref "U$6") (pin "64") (pinfunction "GND_64") (pintype "power_in"))
      (node (ref "U$6") (pin "79") (pinfunction "GND_79") (pintype "power_in"))
      (node (ref "U$6") (pin "82") (pinfunction "GND_82") (pintype "power_in"))
      (node (ref "U$6") (pin "95") (pinfunction "GND_95") (pintype "power_in"))
      (node (ref "U$6") (pin "96") (pinfunction "MSEL1_96") (pintype "input"))
      (node (ref "U$6") (pin "E") (pinfunction "GND_E") (pintype "power_in"))
      (node (ref "U$7") (pin "4") (pinfunction "GND_4") (pintype "passive"))
      (node (ref "U$8") (pin "2") (pinfunction "GND_2") (pintype "bidirectional"))
      (node (ref "U$9") (pin "2") (pinfunction "GND_2") (pintype "bidirectional"))
      (node (ref "U4") (pin "8") (pinfunction "GND_8") (pintype "bidirectional"))
      (node (ref "U5") (pin "8") (pinfunction "GND_8") (pintype "bidirectional"))
    )
    (net (code "56") (name "GREEN_0") (class "Default")
      (node (ref "DISPLAY") (pin "P$13") (pinfunction "P$13_P$13") (pintype "bidirectional"))
      (node (ref "U$6") (pin "43") (pinfunction "IO43_43") (pintype "bidirectional"))
    )
    (net (code "57") (name "GREEN_1") (class "Default")
      (node (ref "DISPLAY") (pin "P$14") (pinfunction "P$14_P$14") (pintype "bidirectional"))
      (node (ref "U$6") (pin "44") (pinfunction "IO44_44") (pintype "bidirectional"))
    )
    (net (code "58") (name "GREEN_2") (class "Default")
      (node (ref "DISPLAY") (pin "P$15") (pinfunction "P$15_P$15") (pintype "bidirectional"))
      (node (ref "U$6") (pin "46") (pinfunction "IO46_46") (pintype "bidirectional"))
    )
    (net (code "59") (name "GREEN_3") (class "Default")
      (node (ref "DISPLAY") (pin "P$16") (pinfunction "P$16_P$16") (pintype "bidirectional"))
      (node (ref "U$6") (pin "49") (pinfunction "IO49_49") (pintype "bidirectional"))
    )
    (net (code "60") (name "GREEN_4") (class "Default")
      (node (ref "DISPLAY") (pin "P$17") (pinfunction "P$17_P$17") (pintype "bidirectional"))
      (node (ref "U$6") (pin "50") (pinfunction "IO50_50") (pintype "bidirectional"))
    )
    (net (code "61") (name "GREEN_5") (class "Default")
      (node (ref "DISPLAY") (pin "P$18") (pinfunction "P$18_P$18") (pintype "bidirectional"))
      (node (ref "U$6") (pin "51") (pinfunction "IO51_51") (pintype "bidirectional"))
    )
    (net (code "62") (name "GREEN_6") (class "Default")
      (node (ref "DISPLAY") (pin "P$19") (pinfunction "P$19_P$19") (pintype "bidirectional"))
      (node (ref "U$6") (pin "52") (pinfunction "IO52_52") (pintype "bidirectional"))
    )
    (net (code "63") (name "GREEN_7") (class "Default")
      (node (ref "DISPLAY") (pin "P$20") (pinfunction "P$20_P$20") (pintype "bidirectional"))
      (node (ref "U$6") (pin "53") (pinfunction "IO53_53") (pintype "bidirectional"))
    )
    (net (code "64") (name "LED1") (class "Default")
      (node (ref "FPGA") (pin "C") (pinfunction "C_C") (pintype "passive"))
      (node (ref "U$6") (pin "144") (pinfunction "IO144_144") (pintype "input"))
    )
    (net (code "65") (name "LED2") (class "Default")
      (node (ref "ATMEGA328P") (pin "14") (pinfunction "PB2_14") (pintype "bidirectional"))
      (node (ref "MICRO") (pin "C") (pinfunction "C_C") (pintype "passive"))
    )
    (net (code "66") (name "MISO") (class "Default")
      (node (ref "ATMEGA328P") (pin "16") (pinfunction "PB4_16") (pintype "bidirectional"))
      (node (ref "ICP") (pin "1") (pinfunction "1_1") (pintype "passive"))
      (node (ref "U$2") (pin "15") (pinfunction "SO_15") (pintype "output"))
    )
    (net (code "67") (name "MOSI") (class "Default")
      (node (ref "ATMEGA328P") (pin "15") (pinfunction "PB3_15") (pintype "bidirectional"))
      (node (ref "ICP") (pin "4") (pinfunction "4_4") (pintype "passive"))
      (node (ref "U$2") (pin "14") (pinfunction "SI_14") (pintype "input"))
    )
    (net (code "68") (name "NCE") (class "Default")
      (node (ref "AS") (pin "6") (pinfunction "6_6") (pintype "passive"))
      (node (ref "R16") (pin "1") (pinfunction "1_1") (pintype "passive"))
      (node (ref "U$6") (pin "21") (pinfunction "NCE_21") (pintype "input"))
    )
    (net (code "69") (name "NCEO") (class "Default")
      (node (ref "U$6") (pin "101") (pinfunction "NCEO_101") (pintype "power_in"))
    )
    (net (code "70") (name "NCONFIG") (class "Default")
      (node (ref "AS") (pin "5") (pinfunction "5_5") (pintype "passive"))
      (node (ref "R14") (pin "1") (pinfunction "1_1") (pintype "passive"))
      (node (ref "U$6") (pin "14") (pinfunction "NCONFIG_14") (pintype "input"))
    )
    (net (code "71") (name "NCSO") (class "Default")
      (node (ref "AS") (pin "8") (pinfunction "8_8") (pintype "passive"))
      (node (ref "U$6") (pin "8") (pinfunction "FLASH_NCE,NCSO_8") (pintype "input"))
      (node (ref "U$7") (pin "1") (pinfunction "NCS_1") (pintype "input"))
    )
    (net (code "72") (name "NOT_CONNECTED") (class "Default")
      (node (ref "DISPLAY") (pin "P$35") (pinfunction "P$35_P$35") (pintype "bidirectional"))
    )
    (net (code "73") (name "Net-(3.3V-PadA)") (class "Default")
      (node (ref "3.3V") (pin "A") (pinfunction "A_A") (pintype "passive"))
      (node (ref "R6") (pin "1") (pinfunction "1_1") (pintype "passive"))
    )
    (net (code "74") (name "Net-(5V-PadA)") (class "Default")
      (node (ref "5V") (pin "A") (pinfunction "A_A") (pintype "passive"))
      (node (ref "R20") (pin "1") (pinfunction "1_1") (pintype "passive"))
    )
    (net (code "75") (name "Net-(C8-Pad1)") (class "Default")
      (node (ref "C8") (pin "1") (pinfunction "1_1") (pintype "passive"))
      (node (ref "R8") (pin "1") (pinfunction "1_1") (pintype "passive"))
    )
    (net (code "76") (name "Net-(C9-Pad1)") (class "Default")
      (node (ref "C9") (pin "1") (pinfunction "1_1") (pintype "passive"))
      (node (ref "R9") (pin "1") (pinfunction "1_1") (pintype "passive"))
    )
    (net (code "77") (name "Net-(FPGA-PadA)") (class "Default")
      (node (ref "FPGA") (pin "A") (pinfunction "A_A") (pintype "passive"))
      (node (ref "R4") (pin "1") (pinfunction "1_1") (pintype "passive"))
    )
    (net (code "78") (name "Net-(L1-2)") (class "Default")
      (node (ref "L1") (pin "P$2") (pinfunction "2_P$2") (pintype "passive"))
      (node (ref "U$11") (pin "1") (pinfunction "SW_1") (pintype "bidirectional"))
      (node (ref "U$14") (pin "2") (pinfunction "A_2") (pintype "bidirectional"))
    )
    (net (code "79") (name "Net-(L5-1)") (class "Default")
      (node (ref "FUSE") (pin "P$1") (pinfunction "1_P$1") (pintype "passive"))
      (node (ref "FUSE") (pin "P$4") (pinfunction "1_P$4") (pintype "passive"))
      (node (ref "L5") (pin "P$1") (pinfunction "1_P$1") (pintype "passive"))
    )
    (net (code "80") (name "Net-(MICRO-PadA)") (class "Default")
      (node (ref "MICRO") (pin "A") (pinfunction "A_A") (pintype "passive"))
      (node (ref "R5") (pin "1") (pinfunction "1_1") (pintype "passive"))
    )
    (net (code "81") (name "Net-(U$3-RS)") (class "Default")
      (node (ref "R10") (pin "2") (pinfunction "2_2") (pintype "passive"))
      (node (ref "U$3") (pin "8") (pinfunction "RS_8") (pintype "input"))
    )
    (net (code "82") (name "Net-(U$6-NSTATUS)") (class "Default")
      (node (ref "R13") (pin "1") (pinfunction "1_1") (pintype "passive"))
      (node (ref "U$6") (pin "9") (pinfunction "NSTATUS_9") (pintype "input"))
    )
    (net (code "83") (name "Net-(U$10-N{slash}C)") (class "Default")
      (node (ref "R17") (pin "2") (pinfunction "2_2") (pintype "passive"))
      (node (ref "R18") (pin "1") (pinfunction "1_1") (pintype "passive"))
      (node (ref "U$10") (pin "4") (pinfunction "N/C_4") (pintype "bidirectional"))
    )
    (net (code "84") (name "PWR_IN_12") (class "Default")
      (node (ref "FUSE") (pin "P$2") (pinfunction "2_P$2") (pintype "passive"))
      (node (ref "FUSE") (pin "P$3") (pinfunction "2_P$3") (pintype "passive"))
      (node (ref "TE_AMPSEAL_8") (pin "8") (pinfunction "2_8") (pintype "passive"))
    )
    (net (code "85") (name "RED_0") (class "Default")
      (node (ref "DISPLAY") (pin "P$5") (pinfunction "P$5_P$5") (pintype "bidirectional"))
      (node (ref "U$6") (pin "28") (pinfunction "IO28_28") (pintype "bidirectional"))
    )
    (net (code "86") (name "RED_1") (class "Default")
      (node (ref "DISPLAY") (pin "P$6") (pinfunction "P$6_P$6") (pintype "bidirectional"))
      (node (ref "U$6") (pin "31") (pinfunction "IO31_31") (pintype "bidirectional"))
    )
    (net (code "87") (name "RED_2") (class "Default")
      (node (ref "DISPLAY") (pin "P$7") (pinfunction "P$7_P$7") (pintype "bidirectional"))
      (node (ref "U$6") (pin "32") (pinfunction "IO32_32") (pintype "bidirectional"))
    )
    (net (code "88") (name "RED_3") (class "Default")
      (node (ref "DISPLAY") (pin "P$8") (pinfunction "P$8_P$8") (pintype "bidirectional"))
      (node (ref "U$6") (pin "33") (pinfunction "IO33_33") (pintype "bidirectional"))
    )
    (net (code "89") (name "RED_4") (class "Default")
      (node (ref "DISPLAY") (pin "P$9") (pinfunction "P$9_P$9") (pintype "bidirectional"))
      (node (ref "U$6") (pin "34") (pinfunction "IO34_34") (pintype "bidirectional"))
    )
    (net (code "90") (name "RED_5") (class "Default")
      (node (ref "DISPLAY") (pin "P$10") (pinfunction "P$10_P$10") (pintype "bidirectional"))
      (node (ref "U$6") (pin "38") (pinfunction "IO38_38") (pintype "bidirectional"))
    )
    (net (code "91") (name "RED_6") (class "Default")
      (node (ref "DISPLAY") (pin "P$11") (pinfunction "P$11_P$11") (pintype "bidirectional"))
      (node (ref "U$6") (pin "39") (pinfunction "IO39_39") (pintype "bidirectional"))
    )
    (net (code "92") (name "RED_7") (class "Default")
      (node (ref "DISPLAY") (pin "P$12") (pinfunction "P$12_P$12") (pintype "bidirectional"))
      (node (ref "U$6") (pin "42") (pinfunction "IO42_42") (pintype "bidirectional"))
    )
    (net (code "93") (name "RESET") (class "Default")
      (node (ref "ATMEGA328P") (pin "29") (pinfunction "PC6_29") (pintype "bidirectional"))
      (node (ref "ICP") (pin "5") (pinfunction "5_5") (pintype "passive"))
      (node (ref "R7") (pin "1") (pinfunction "1_1") (pintype "passive"))
      (node (ref "U$2") (pin "17") (pinfunction "~{RESET}_17") (pintype "input"))
    )
    (net (code "94") (name "RXCAN") (class "Default")
      (node (ref "U$2") (pin "2") (pinfunction "RXCAN_2") (pintype "input"))
      (node (ref "U$3") (pin "4") (pinfunction "RXD_4") (pintype "output"))
    )
    (net (code "95") (name "RXD") (class "Default")
      (node (ref "ATMEGA328P") (pin "30") (pinfunction "PD0_30") (pintype "bidirectional"))
    )
    (net (code "96") (name "SCK") (class "Default")
      (node (ref "ATMEGA328P") (pin "17") (pinfunction "PB5_17") (pintype "bidirectional"))
      (node (ref "ICP") (pin "3") (pinfunction "3_3") (pintype "passive"))
      (node (ref "U$2") (pin "13") (pinfunction "SCK_13") (pintype "input"))
    )
    (net (code "97") (name "TCK") (class "Default")
      (node (ref "JTAG") (pin "1") (pinfunction "1_1") (pintype "passive"))
      (node (ref "R2") (pin "2") (pinfunction "2_2") (pintype "passive"))
      (node (ref "U$6") (pin "16") (pinfunction "TCK_16") (pintype "input"))
    )
    (net (code "98") (name "TDI") (class "Default")
      (node (ref "JTAG") (pin "9") (pinfunction "9_9") (pintype "passive"))
      (node (ref "R11") (pin "2") (pinfunction "2_2") (pintype "passive"))
      (node (ref "U$6") (pin "15") (pinfunction "TDI_15") (pintype "input"))
    )
    (net (code "99") (name "TDO") (class "Default")
      (node (ref "JTAG") (pin "3") (pinfunction "3_3") (pintype "passive"))
      (node (ref "U$6") (pin "20") (pinfunction "TDO_20") (pintype "output"))
    )
    (net (code "100") (name "TMS") (class "Default")
      (node (ref "JTAG") (pin "5") (pinfunction "5_5") (pintype "passive"))
      (node (ref "R12") (pin "1") (pinfunction "1_1") (pintype "passive"))
      (node (ref "U$6") (pin "18") (pinfunction "TMS_18") (pintype "input"))
    )
    (net (code "101") (name "TXCAN") (class "Default")
      (node (ref "U$2") (pin "1") (pinfunction "TXCAN_1") (pintype "output"))
      (node (ref "U$3") (pin "1") (pinfunction "TXD_1") (pintype "input"))
    )
    (net (code "102") (name "TXD") (class "Default")
      (node (ref "ATMEGA328P") (pin "31") (pinfunction "PD1_31") (pintype "bidirectional"))
    )
    (net (code "103") (name "V+") (class "Default")
      (node (ref "2.5T") (pin "TP") (pinfunction "TP_TP") (pintype "input"))
      (node (ref "C15") (pin "1") (pinfunction "1_1") (pintype "passive"))
      (node (ref "R17") (pin "1") (pinfunction "1_1") (pintype "passive"))
      (node (ref "U$10") (pin "5") (pinfunction "VOUT_5") (pintype "bidirectional"))
      (node (ref "U$6") (pin "107") (pinfunction "VCCA2_107") (pintype "power_in"))
      (node (ref "U$6") (pin "35") (pinfunction "VCCA1_35") (pintype "power_in"))
      (node (ref "U$6") (pin "94") (pinfunction "MSEL0_94") (pintype "input"))
      (node (ref "U$6") (pin "97") (pinfunction "MSEL2_97") (pintype "input"))
    )
    (net (code "104") (name "VCC") (class "Default")
      (node (ref "1.2T") (pin "TP") (pinfunction "TP_TP") (pintype "input"))
      (node (ref "C1") (pin "1") (pinfunction "1_1") (pintype "passive"))
      (node (ref "C21") (pin "1") (pinfunction "1_1") (pintype "passive"))
      (node (ref "C22") (pin "1") (pinfunction "1_1") (pintype "passive"))
      (node (ref "C23") (pin "1") (pinfunction "1_1") (pintype "passive"))
      (node (ref "U$5") (pin "2") (pinfunction "VOUT_2") (pintype "output"))
      (node (ref "U$6") (pin "102") (pinfunction "VINT_102") (pintype "power_in"))
      (node (ref "U$6") (pin "109") (pinfunction "VCC_PLL2_109") (pintype "power_in"))
      (node (ref "U$6") (pin "116") (pinfunction "VINT_116") (pintype "power_in"))
      (node (ref "U$6") (pin "134") (pinfunction "VINT_134") (pintype "power_in"))
      (node (ref "U$6") (pin "29") (pinfunction "VINT_29") (pintype "power_in"))
      (node (ref "U$6") (pin "37") (pinfunction "VCC_PLL1_37") (pintype "power_in"))
      (node (ref "U$6") (pin "45") (pinfunction "VINT_45") (pintype "power_in"))
      (node (ref "U$6") (pin "5") (pinfunction "VINT_5") (pintype "power_in"))
      (node (ref "U$6") (pin "61") (pinfunction "VINT_61") (pintype "power_in"))
      (node (ref "U$6") (pin "78") (pinfunction "VINT_78") (pintype "power_in"))
    )
    (net (code "105") (name "XTAL1") (class "Default")
      (node (ref "ATMEGA328P") (pin "7") (pinfunction "PB6_7") (pintype "bidirectional"))
      (node (ref "C3") (pin "2") (pinfunction "2_2") (pintype "passive"))
      (node (ref "U$4") (pin "3") (pinfunction "2_3") (pintype "passive"))
    )
    (net (code "106") (name "XTAL2") (class "Default")
      (node (ref "ATMEGA328P") (pin "8") (pinfunction "PB7_8") (pintype "bidirectional"))
      (node (ref "C4") (pin "1") (pinfunction "1_1") (pintype "passive"))
      (node (ref "U$4") (pin "1") (pinfunction "1_1") (pintype "passive"))
    )
    (net (code "107") (name "unconnected-(ATMEGA328P-ADC6-Pad19)") (class "Default")
      (node (ref "ATMEGA328P") (pin "19") (pinfunction "ADC6_19") (pintype "input"))
    )
    (net (code "108") (name "unconnected-(ATMEGA328P-ADC7-Pad22)") (class "Default")
      (node (ref "ATMEGA328P") (pin "22") (pinfunction "ADC7_22") (pintype "input"))
    )
    (net (code "109") (name "unconnected-(ATMEGA328P-AREF-Pad20)") (class "Default")
      (node (ref "ATMEGA328P") (pin "20") (pinfunction "AREF_20") (pintype "input"))
    )
    (net (code "110") (name "unconnected-(ATMEGA328P-PB0-Pad12)") (class "Default")
      (node (ref "ATMEGA328P") (pin "12") (pinfunction "PB0_12") (pintype "bidirectional"))
    )
    (net (code "111") (name "unconnected-(JTAG-Pad6)") (class "Default")
      (node (ref "JTAG") (pin "6") (pinfunction "6_6") (pintype "passive"))
    )
    (net (code "112") (name "unconnected-(JTAG-Pad7)") (class "Default")
      (node (ref "JTAG") (pin "7") (pinfunction "7_7") (pintype "passive"))
    )
    (net (code "113") (name "unconnected-(JTAG-Pad8)") (class "Default")
      (node (ref "JTAG") (pin "8") (pinfunction "8_8") (pintype "passive"))
    )
    (net (code "114") (name "unconnected-(U$1-E{slash}D-Pad1)") (class "Default")
      (node (ref "U$1") (pin "1") (pinfunction "E/D_1") (pintype "input"))
    )
    (net (code "115") (name "unconnected-(U$2-CLKOUT{slash}SOF-Pad3)") (class "Default")
      (node (ref "U$2") (pin "3") (pinfunction "CLKOUT/SOF_3") (pintype "output"))
    )
    (net (code "116") (name "unconnected-(U$2-~{RX0BF}-Pad11)") (class "Default")
      (node (ref "U$2") (pin "11") (pinfunction "~{RX0BF}_11") (pintype "output"))
    )
    (net (code "117") (name "unconnected-(U$2-~{RX1BF}-Pad10)") (class "Default")
      (node (ref "U$2") (pin "10") (pinfunction "~{RX1BF}_10") (pintype "output"))
    )
    (net (code "118") (name "unconnected-(U$2-~{TX0RTS}-Pad4)") (class "Default")
      (node (ref "U$2") (pin "4") (pinfunction "~{TX0RTS}_4") (pintype "input"))
    )
    (net (code "119") (name "unconnected-(U$2-~{TX1RTS}-Pad5)") (class "Default")
      (node (ref "U$2") (pin "5") (pinfunction "~{TX1RTS}_5") (pintype "input"))
    )
    (net (code "120") (name "unconnected-(U$2-~{TX2RTS}-Pad6)") (class "Default")
      (node (ref "U$2") (pin "6") (pinfunction "~{TX2RTS}_6") (pintype "input"))
    )
    (net (code "121") (name "unconnected-(U$3-VREF-Pad5)") (class "Default")
      (node (ref "U$3") (pin "5") (pinfunction "VREF_5") (pintype "output"))
    )
    (net (code "122") (name "unconnected-(U$6-CLK2-Pad24)") (class "Default")
      (node (ref "U$6") (pin "24") (pinfunction "CLK2_24") (pintype "input"))
    )
    (net (code "123") (name "unconnected-(U$6-CLK3-Pad25)") (class "Default")
      (node (ref "U$6") (pin "25") (pinfunction "CLK3_25") (pintype "input"))
    )
    (net (code "124") (name "unconnected-(U$6-CLK4-Pad91)") (class "Default")
      (node (ref "U$6") (pin "91") (pinfunction "CLK4_91") (pintype "input"))
    )
    (net (code "125") (name "unconnected-(U$6-CLK5-Pad90)") (class "Default")
      (node (ref "U$6") (pin "90") (pinfunction "CLK5_90") (pintype "input"))
    )
    (net (code "126") (name "unconnected-(U$6-CLK6-Pad89)") (class "Default")
      (node (ref "U$6") (pin "89") (pinfunction "CLK6_89") (pintype "input"))
    )
    (net (code "127") (name "unconnected-(U$6-CLK7-Pad88)") (class "Default")
      (node (ref "U$6") (pin "88") (pinfunction "CLK7_88") (pintype "input"))
    )
    (net (code "128") (name "unconnected-(U$6-CRC_ERROR-Pad99)") (class "Default")
      (node (ref "U$6") (pin "99") (pinfunction "CRC_ERROR_99") (pintype "input"))
    )
    (net (code "129") (name "unconnected-(U$6-INIT_DONE-Pad98)") (class "Default")
      (node (ref "U$6") (pin "98") (pinfunction "INIT_DONE_98") (pintype "input"))
    )
    (net (code "130") (name "unconnected-(U$6-IO1-Pad1)") (class "Default")
      (node (ref "U$6") (pin "1") (pinfunction "IO1_1") (pintype "passive"))
    )
    (net (code "131") (name "unconnected-(U$6-IO2-Pad2)") (class "Default")
      (node (ref "U$6") (pin "2") (pinfunction "IO2_2") (pintype "passive"))
    )
    (net (code "132") (name "unconnected-(U$6-IO3-Pad3)") (class "Default")
      (node (ref "U$6") (pin "3") (pinfunction "IO3_3") (pintype "output"))
    )
    (net (code "133") (name "unconnected-(U$6-IO7-Pad7)") (class "Default")
      (node (ref "U$6") (pin "7") (pinfunction "IO7_7") (pintype "output"))
    )
    (net (code "134") (name "unconnected-(U$6-IO10-Pad10)") (class "Default")
      (node (ref "U$6") (pin "10") (pinfunction "IO10_10") (pintype "bidirectional"))
    )
    (net (code "135") (name "unconnected-(U$6-IO11-Pad11)") (class "Default")
      (node (ref "U$6") (pin "11") (pinfunction "IO11_11") (pintype "bidirectional"))
    )
    (net (code "136") (name "unconnected-(U$6-IO111-Pad111)") (class "Default")
      (node (ref "U$6") (pin "111") (pinfunction "IO111_111") (pintype "bidirectional"))
    )
    (net (code "137") (name "unconnected-(U$6-IO112-Pad112)") (class "Default")
      (node (ref "U$6") (pin "112") (pinfunction "IO112_112") (pintype "bidirectional"))
    )
    (net (code "138") (name "unconnected-(U$6-IO113-Pad113)") (class "Default")
      (node (ref "U$6") (pin "113") (pinfunction "IO113_113") (pintype "bidirectional"))
    )
    (net (code "139") (name "unconnected-(U$6-IO114-Pad114)") (class "Default")
      (node (ref "U$6") (pin "114") (pinfunction "IO114_114") (pintype "bidirectional"))
    )
    (net (code "140") (name "unconnected-(U$6-IO115-Pad115)") (class "Default")
      (node (ref "U$6") (pin "115") (pinfunction "IO115_115") (pintype "bidirectional"))
    )
    (net (code "141") (name "unconnected-(U$6-IO119-Pad119)") (class "Default")
      (node (ref "U$6") (pin "119") (pinfunction "IO119_119") (pintype "bidirectional"))
    )
    (net (code "142") (name "unconnected-(U$6-IO120-Pad120)") (class "Default")
      (node (ref "U$6") (pin "120") (pinfunction "IO120_120") (pintype "bidirectional"))
    )
    (net (code "143") (name "unconnected-(U$6-IO121-Pad121)") (class "Default")
      (node (ref "U$6") (pin "121") (pinfunction "IO121_121") (pintype "bidirectional"))
    )
    (net (code "144") (name "unconnected-(U$6-IO124-Pad124)") (class "Default")
      (node (ref "U$6") (pin "124") (pinfunction "IO124_124") (pintype "bidirectional"))
    )
    (net (code "145") (name "unconnected-(U$6-IO125-Pad125)") (class "Default")
      (node (ref "U$6") (pin "125") (pinfunction "IO125_125") (pintype "bidirectional"))
    )
    (net (code "146") (name "unconnected-(U$6-IO126-Pad126)") (class "Default")
      (node (ref "U$6") (pin "126") (pinfunction "IO126_126") (pintype "bidirectional"))
    )
    (net (code "147") (name "unconnected-(U$6-IO127-Pad127)") (class "Default")
      (node (ref "U$6") (pin "127") (pinfunction "IO127_127") (pintype "bidirectional"))
    )
    (net (code "148") (name "unconnected-(U$6-IO128-Pad128)") (class "Default")
      (node (ref "U$6") (pin "128") (pinfunction "IO128_128") (pintype "bidirectional"))
    )
    (net (code "149") (name "unconnected-(U$6-IO129-Pad129)") (class "Default")
      (node (ref "U$6") (pin "129") (pinfunction "IO129_129") (pintype "bidirectional"))
    )
    (net (code "150") (name "unconnected-(U$6-IO132-Pad132)") (class "Default")
      (node (ref "U$6") (pin "132") (pinfunction "IO132_132") (pintype "bidirectional"))
    )
    (net (code "151") (name "unconnected-(U$6-IO133-Pad133)") (class "Default")
      (node (ref "U$6") (pin "133") (pinfunction "IO133_133") (pintype "bidirectional"))
    )
    (net (code "152") (name "unconnected-(U$6-IO135-Pad135)") (class "Default")
      (node (ref "U$6") (pin "135") (pinfunction "IO135_135") (pintype "bidirectional"))
    )
    (net (code "153") (name "unconnected-(U$6-IO136-Pad136)") (class "Default")
      (node (ref "U$6") (pin "136") (pinfunction "IO136_136") (pintype "bidirectional"))
    )
    (net (code "154") (name "unconnected-(U$6-IO137-Pad137)") (class "Default")
      (node (ref "U$6") (pin "137") (pinfunction "IO137_137") (pintype "input"))
    )
    (net (code "155") (name "unconnected-(U$6-IO138-Pad138)") (class "Default")
      (node (ref "U$6") (pin "138") (pinfunction "IO138_138") (pintype "input"))
    )
    (net (code "156") (name "unconnected-(U$6-IO141-Pad141)") (class "Default")
      (node (ref "U$6") (pin "141") (pinfunction "IO141_141") (pintype "input"))
    )
    (net (code "157") (name "unconnected-(U$6-IO142-Pad142)") (class "Default")
      (node (ref "U$6") (pin "142") (pinfunction "IO142_142") (pintype "input"))
    )
    (net (code "158") (name "unconnected-(U$6-IO143-Pad143)") (class "Default")
      (node (ref "U$6") (pin "143") (pinfunction "IO143_143") (pintype "input"))
    )
    (net (code "159") (name "unconnected-(U5-5A-Pad11)") (class "Default")
      (node (ref "U5") (pin "11") (pinfunction "5A_11") (pintype "bidirectional"))
    )
    (net (code "160") (name "unconnected-(U5-5Y-Pad12)") (class "Default")
      (node (ref "U5") (pin "12") (pinfunction "5Y_12") (pintype "bidirectional"))
    )
    (net (code "161") (name "unconnected-(U5-6A-Pad14)") (class "Default")
      (node (ref "U5") (pin "14") (pinfunction "6A_14") (pintype "bidirectional"))
    )
    (net (code "162") (name "unconnected-(U5-6Y-Pad15)") (class "Default")
      (node (ref "U5") (pin "15") (pinfunction "6Y_15") (pintype "bidirectional"))
    )
    (net (code "163") (name "~{CS_CAN}") (class "Default")
      (node (ref "ATMEGA328P") (pin "28") (pinfunction "PC5_28") (pintype "bidirectional"))
      (node (ref "U$2") (pin "16") (pinfunction "~{CS}_16") (pintype "input"))
    )
    (net (code "164") (name "~{INT_CAN}") (class "Default")
      (node (ref "ATMEGA328P") (pin "32") (pinfunction "PD2_32") (pintype "bidirectional"))
      (node (ref "U$2") (pin "12") (pinfunction "~{INT}_12") (pintype "output"))
    )
  )
)
